# infrared_receiver_controller.net
KiCad netlist of a schematic drawn in EAGLE
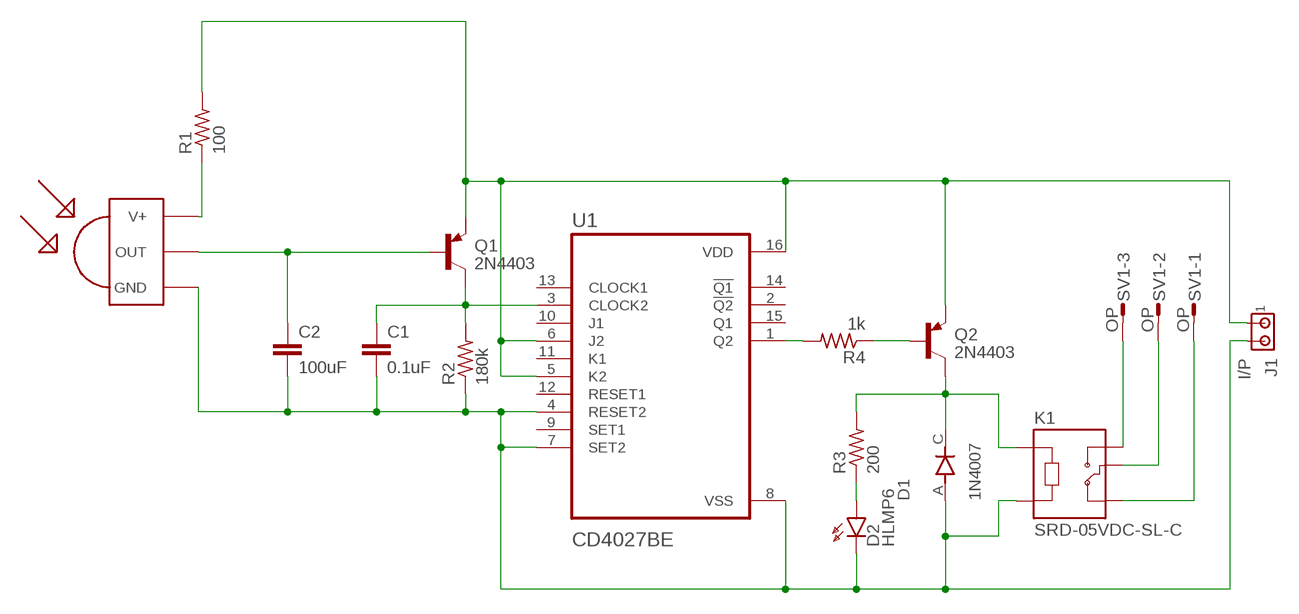
[diagram p0: schematic, sheet 1]

(export (version "E")
  (design (tool "Eeschema 10.0.6"))
  (components
    (comp (ref "C1")
      (value "0.1uF")
      (footprint "eagle-import:C2.5-2")
      (libsource (lib "eagle-import") (part "C2.5/2"))
    )
    (comp (ref "C2")
      (value "100uF")
      (footprint "eagle-import:C2.5-2")
      (libsource (lib "eagle-import") (part "C2.5/2"))
    )
    (comp (ref "D1")
      (value "1N4007")
      (footprint "eagle-import:DIOAD1060W80L520D270")
      (fields (field (name "MF") "Diotec Semiconductor"))
      (libsource (lib "eagle-import") (part "1N4007"))
    )
    (comp (ref "D2")
      (value "HLMP6")
      (footprint "eagle-import:HLMP6")
      (fields (field (name "MF") "AGILENT TECHNOLOGIES") (field (name "MPN") "HLMP-6500"))
      (libsource (lib "eagle-import") (part "HLMP6"))
    )
    (comp (ref "J1")
      (value "I/P")
      (footprint "eagle-import:10X02MTA")
      (libsource (lib "eagle-import") (part "MTA02-100"))
    )
    (comp (ref "K1")
      (value "SRD-05VDC-SL-C")
      (footprint "eagle-import:RELAY_SRD-05VDC-SL-C")
      (fields (field (name "MF") "Songle Relay"))
      (libsource (lib "eagle-import") (part "SRD-05VDC-SL-C"))
    )
    (comp (ref "Q1")
      (value "2N4403")
      (footprint "eagle-import:TO92")
      (fields (field (name "MF") "Central Semiconductor"))
      (libsource (lib "eagle-import") (part "2N4403"))
    )
    (comp (ref "Q2")
      (value "2N4403")
      (footprint "eagle-import:TO92")
      (fields (field (name "MF") "Central Semiconductor"))
      (libsource (lib "eagle-import") (part "2N4403"))
    )
    (comp (ref "R1")
      (value "100")
      (footprint "eagle-import:0204_7")
      (libsource (lib "eagle-import") (part "R-US_0204/7"))
    )
    (comp (ref "R2")
      (value "180k")
      (footprint "eagle-import:0204_7")
      (libsource (lib "eagle-import") (part "R-US_0204/7"))
    )
    (comp (ref "R3")
      (value "200")
      (footprint "eagle-import:0204_7")
      (libsource (lib "eagle-import") (part "R-US_0204/7"))
    )
    (comp (ref "R4")
      (value "1k")
      (footprint "eagle-import:0204_7")
      (libsource (lib "eagle-import") (part "R-US_0204/7"))
    )
    (comp (ref "SV1")
      (value "OP")
      (footprint "eagle-import:L03P")
      (libsource (lib "eagle-import") (part "L03P"))
    )
    (comp (ref "U$1")
      (value "TSOP1738")
      (footprint "eagle-import:TSOP17XX")
      (fields (field (name "MF") "Vishay") (field (name "MP") "TSOP1738."))
      (libsource (lib "eagle-import") (part "TSOP1738"))
    )
    (comp (ref "U1")
      (value "CD4027BE")
      (footprint "eagle-import:DIP794W45P254L1969H508Q16")
      (fields (field (name "MF") "Texas Instruments"))
      (libsource (lib "eagle-import") (part "CD4027BE"))
    )
  )
  (nets
    (net (code "1") (name "Net-(D2-PadA)") (class "Default")
      (node (ref "D2") (pin "A") (pinfunction "A_A") (pintype "passive"))
      (node (ref "R3") (pin "1") (pinfunction "1_1") (pintype "passive"))
    )
    (net (code "2") (name "Net-(Q1-B)") (class "Default")
      (node (ref "C2") (pin "1") (pinfunction "1_1") (pintype "passive"))
      (node (ref "Q1") (pin "2") (pinfunction "B_2") (pintype "passive"))
      (node (ref "U$1") (pin "OUT") (pinfunction "OUT_OUT") (pintype "bidirectional"))
    )
    (net (code "3") (name "Net-(Q1-C)") (class "Default")
      (node (ref "C1") (pin "1") (pinfunction "1_1") (pintype "passive"))
      (node (ref "Q1") (pin "3") (pinfunction "C_3") (pintype "passive"))
      (node (ref "R2") (pin "2") (pinfunction "2_2") (pintype "passive"))
      (node (ref "U1") (pin "3") (pinfunction "CLOCK2_3") (pintype "input"))
    )
    (net (code "4") (name "Net-(Q1-E)") (class "Default")
      (node (ref "J1") (pin "1") (pinfunction "1_1") (pintype "passive"))
      (node (ref "Q1") (pin "1") (pinfunction "E_1") (pintype "passive"))
      (node (ref "Q2") (pin "1") (pinfunction "E_1") (pintype "passive"))
      (node (ref "R1") (pin "2") (pinfunction "2_2") (pintype "passive"))
      (node (ref "U1") (pin "16") (pinfunction "VDD_16") (pintype "power_in"))
      (node (ref "U1") (pin "5") (pinfunction "K2_5") (pintype "input"))
      (node (ref "U1") (pin "6") (pinfunction "J2_6") (pintype "input"))
    )
    (net (code "5") (name "Net-(Q2-B)") (class "Default")
      (node (ref "Q2") (pin "2") (pinfunction "B_2") (pintype "passive"))
      (node (ref "R4") (pin "1") (pinfunction "1_1") (pintype "passive"))
    )
    (net (code "6") (name "Net-(Q2-C)") (class "Default")
      (node (ref "D1") (pin "C") (pinfunction "C_C") (pintype "passive"))
      (node (ref "K1") (pin "A1") (pinfunction "A1_A1") (pintype "passive"))
      (node (ref "Q2") (pin "3") (pinfunction "C_3") (pintype "passive"))
      (node (ref "R3") (pin "2") (pinfunction "2_2") (pintype "passive"))
    )
    (net (code "7") (name "Net-(R1-Pad1)") (class "Default")
      (node (ref "R1") (pin "1") (pinfunction "1_1") (pintype "passive"))
      (node (ref "U$1") (pin "V+") (pinfunction "V+_V+") (pintype "bidirectional"))
    )
    (net (code "8") (name "Net-(SV1A-S)") (class "Default")
      (node (ref "K1") (pin "NC") (pinfunction "NC_NC") (pintype "passive"))
      (node (ref "SV1") (pin "1") (pinfunction "S_1") (pintype "passive"))
    )
    (net (code "9") (name "Net-(SV1B-S)") (class "Default")
      (node (ref "K1") (pin "COM") (pinfunction "COM_COM") (pintype "passive"))
      (node (ref "SV1") (pin "2") (pinfunction "S_2") (pintype "passive"))
    )
    (net (code "10") (name "Net-(SV1C-S)") (class "Default")
      (node (ref "K1") (pin "NO") (pinfunction "NO_NO") (pintype "passive"))
      (node (ref "SV1") (pin "3") (pinfunction "S_3") (pintype "passive"))
    )
    (net (code "11") (name "Net-(U1-Q2)") (class "Default")
      (node (ref "R4") (pin "2") (pinfunction "2_2") (pintype "passive"))
      (node (ref "U1") (pin "1") (pinfunction "Q2_1") (pintype "output"))
    )
    (net (code "12") (name "Net-(U1-RESET2)") (class "Default")
      (node (ref "C1") (pin "2") (pinfunction "2_2") (pintype "passive"))
      (node (ref "C2") (pin "2") (pinfunction "2_2") (pintype "passive"))
      (node (ref "D1") (pin "A") (pinfunction "A_A") (pintype "passive"))
      (node (ref "D2") (pin "K") (pinfunction "K_K") (pintype "passive"))
      (node (ref "J1") (pin "2") (pinfunction "2_2") (pintype "passive"))
      (node (ref "K1") (pin "A2") (pinfunction "A2_A2") (pintype "passive"))
      (node (ref "R2") (pin "1") (pinfunction "1_1") (pintype "passive"))
      (node (ref "U$1") (pin "GND") (pinfunction "GND_GND") (pintype "bidirectional"))
      (node (ref "U1") (pin "4") (pinfunction "RESET2_4") (pintype "input"))
      (node (ref "U1") (pin "7") (pinfunction "SET2_7") (pintype "input"))
      (node (ref "U1") (pin "8") (pinfunction "VSS_8") (pintype "power_in"))
    )
    (net (code "13") (name "unconnected-(U1-CLOCK1-Pad13)") (class "Default")
      (node (ref "U1") (pin "13") (pinfunction "CLOCK1_13") (pintype "input"))
    )
    (net (code "14") (name "unconnected-(U1-J1-Pad10)") (class "Default")
      (node (ref "U1") (pin "10") (pinfunction "J1_10") (pintype "input"))
    )
    (net (code "15") (name "unconnected-(U1-K1-Pad11)") (class "Default")
      (node (ref "U1") (pin "11") (pinfunction "K1_11") (pintype "input"))
    )
    (net (code "16") (name "unconnected-(U1-Q1-Pad15)") (class "Default")
      (node (ref "U1") (pin "15") (pinfunction "Q1_15") (pintype "output"))
    )
    (net (code "17") (name "unconnected-(U1-RESET1-Pad12)") (class "Default")
      (node (ref "U1") (pin "12") (pinfunction "RESET1_12") (pintype "input"))
    )
    (net (code "18") (name "unconnected-(U1-SET1-Pad9)") (class "Default")
      (node (ref "U1") (pin "9") (pinfunction "SET1_9") (pintype "input"))
    )
    (net (code "19") (name "unconnected-(U1-~{Q1}-Pad14)") (class "Default")
      (node (ref "U1") (pin "14") (pinfunction "~{Q1}_14") (pintype "output"))
    )
    (net (code "20") (name "unconnected-(U1-~{Q2}-Pad2)") (class "Default")
      (node (ref "U1") (pin "2") (pinfunction "~{Q2}_2") (pintype "output"))
    )
  )
)
